# ECAM02-EE2_0.net
KiCad netlist of a schematic drawn in EAGLE
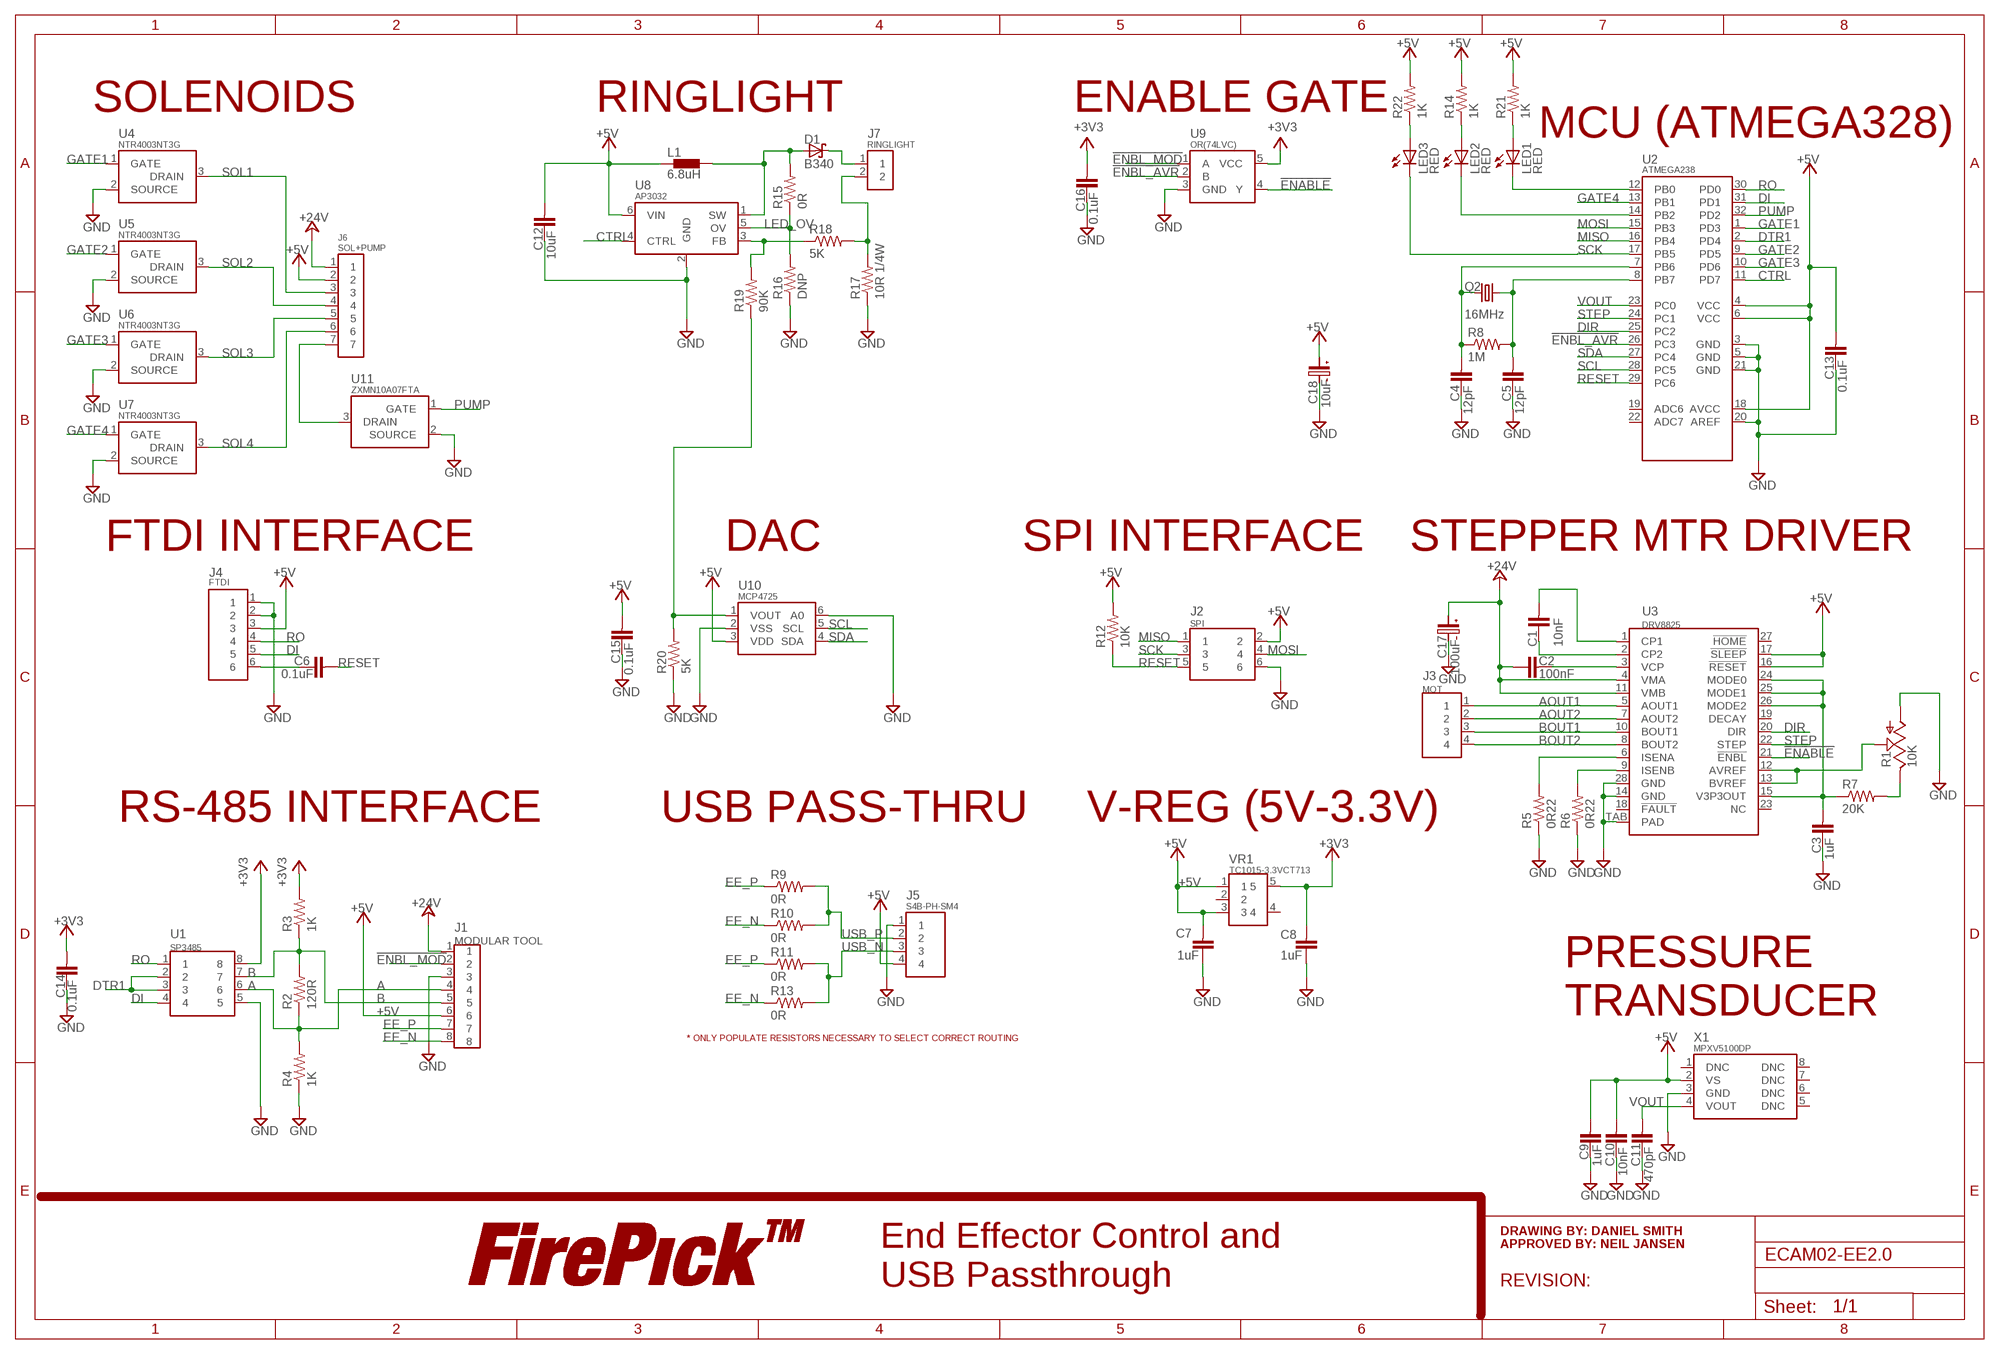
[diagram p0: schematic, sheet 1]

(export (version "E")
  (design (tool "Eeschema 10.0.6"))
  (components
    (comp (ref "C1")
      (value "10nF")
      (footprint "eagle-import:C0603")
      (fields (field (name "PARTNO") "GRM188R71H103KA01D"))
      (libsource (lib "eagle-import") (part "CPL-CAP-X7R-0603-10NF-50V"))
    )
    (comp (ref "C2")
      (value "100nF")
      (footprint "eagle-import:C0603")
      (fields (field (name "PARTNO") "UMK107B7104KA-T"))
      (libsource (lib "eagle-import") (part "CPL-CAP-X7R-0603-100NF-50V"))
    )
    (comp (ref "C3")
      (value "1uF")
      (footprint "eagle-import:C0603")
      (fields (field (name "PARTNO") "UMK107AB7105KA-T"))
      (libsource (lib "eagle-import") (part "CPL-CAP-X5R-0603-1UF-50V"))
    )
    (comp (ref "C4")
      (value "12pF")
      (footprint "eagle-import:C0603")
      (fields (field (name "PARTNO") "GRM1885C1H120FA01J"))
      (libsource (lib "eagle-import") (part "CPL-CAP-C0G-0603-12PF-50V"))
    )
    (comp (ref "C5")
      (value "12pF")
      (footprint "eagle-import:C0603")
      (fields (field (name "PARTNO") "GRM1885C1H120FA01J"))
      (libsource (lib "eagle-import") (part "CPL-CAP-C0G-0603-12PF-50V"))
    )
    (comp (ref "C6")
      (value "0.1uF")
      (footprint "eagle-import:C0603")
      (fields (field (name "PARTNO") "UMK107B7104KA-T"))
      (libsource (lib "eagle-import") (part "CPL-CAP-X7R-0603-100NF-50V"))
    )
    (comp (ref "C7")
      (value "1uF")
      (footprint "eagle-import:C0603")
      (fields (field (name "PARTNO") "UMK107AB7105KA-T"))
      (libsource (lib "eagle-import") (part "CPL-CAP-X5R-0603-1UF-50V"))
    )
    (comp (ref "C8")
      (value "1uF")
      (footprint "eagle-import:C0603")
      (fields (field (name "PARTNO") "UMK107AB7105KA-T"))
      (libsource (lib "eagle-import") (part "CPL-CAP-X5R-0603-1UF-50V"))
    )
    (comp (ref "C9")
      (value "1uF")
      (footprint "eagle-import:C0603")
      (fields (field (name "PARTNO") "UMK107AB7105KA-T"))
      (libsource (lib "eagle-import") (part "CPL-CAP-X5R-0603-1UF-50V"))
    )
    (comp (ref "C10")
      (value "10nF")
      (footprint "eagle-import:C0603")
      (fields (field (name "PARTNO") "GRM188R71H103KA01D"))
      (libsource (lib "eagle-import") (part "CPL-CAP-X7R-0603-10NF-50V"))
    )
    (comp (ref "C11")
      (value "470pF")
      (footprint "eagle-import:C0603")
      (fields (field (name "PARTNO") "GRM188R72A471KA01D"))
      (libsource (lib "eagle-import") (part "CPL-CAP-X7R-0603-470PF-100V"))
    )
    (comp (ref "C12")
      (value "10uF")
      (footprint "eagle-import:C0603")
      (fields (field (name "PARTNO") "GRM188R61C106MA73D"))
      (libsource (lib "eagle-import") (part "CPL-CAP-X5R-0603-10UF-25V"))
    )
    (comp (ref "C13")
      (value "0.1uF")
      (footprint "eagle-import:C0603")
      (fields (field (name "PARTNO") "GMK107BJ104KAHT"))
      (libsource (lib "eagle-import") (part "CPL-CAP-X7R-0603-0.1UF-35V"))
    )
    (comp (ref "C14")
      (value "0.1uF")
      (footprint "eagle-import:C0603")
      (fields (field (name "PARTNO") "GMK107BJ104KAHT"))
      (libsource (lib "eagle-import") (part "CPL-CAP-X7R-0603-0.1UF-35V"))
    )
    (comp (ref "C15")
      (value "0.1uF")
      (footprint "eagle-import:C0603")
      (fields (field (name "PARTNO") "GMK107BJ104KAHT"))
      (libsource (lib "eagle-import") (part "CPL-CAP-X7R-0603-0.1UF-35V"))
    )
    (comp (ref "C16")
      (value "0.1uF")
      (footprint "eagle-import:C0603")
      (fields (field (name "PARTNO") "GMK107BJ104KAHT"))
      (libsource (lib "eagle-import") (part "CPL-CAP-X7R-0603-0.1UF-35V"))
    )
    (comp (ref "C17")
      (value "100uF")
      (footprint "eagle-import:C-SMD-6.3MM")
      (fields (field (name "PARTNO") "EMVA500ADA101MHA0G"))
      (libsource (lib "eagle-import") (part "CPL-CAP-ALU-SMD-100UF-50V"))
    )
    (comp (ref "C18")
      (value "10uF")
      (footprint "eagle-import:C-SMD-6.3MM")
      (fields (field (name "PARTNO") "EMVH350ADA100MF60G"))
      (libsource (lib "eagle-import") (part "CPL-CAP-ALU-6.4MM-10UF-10V"))
    )
    (comp (ref "D1")
      (value "B340")
      (footprint "eagle-import:DIO-SMA")
      (fields (field (name "PARTNO") "B340A-13-F"))
      (libsource (lib "eagle-import") (part "CPL-DIO-B340-13-F-SMA"))
    )
    (comp (ref "J1")
      (value "MODULAR TOOL")
      (footprint "eagle-import:CON-JST-PH-2.0MM-8P-SMT-VRT")
      (fields (field (name "PARTNO") "B8B-PH-SM4-TB(LF)(SN)"))
      (libsource (lib "eagle-import") (part "CPL-CON-JST-2.0MM-8P-SMT-VRT"))
    )
    (comp (ref "J2")
      (value "SPI")
      (footprint "eagle-import:CON-HDR-2X3P")
      (fields (field (name "PARTNO") "67996-206HLF"))
      (libsource (lib "eagle-import") (part "CPL-CON-HEADER-0.1IN-2X3P-M"))
    )
    (comp (ref "J3")
      (value "MOT")
      (footprint "eagle-import:CON-JST-PH-2.0MM-4P-THRU-VRT")
      (fields (field (name "PARTNO") "B4B-PH-K-S(LF)(SN)"))
      (libsource (lib "eagle-import") (part "CPL-CON-JST-2.0MM-4P-M-THRU-VRT"))
    )
    (comp (ref "J4")
      (value "FTDI")
      (footprint "eagle-import:CON-HDR-6POS-MALE")
      (fields (field (name "PARTNO") "S6B-PH-SM4-TB(LF)(SN)"))
      (libsource (lib "eagle-import") (part "CPL-CON-HEADER-0.1IN-6P-M"))
    )
    (comp (ref "J5")
      (value "S4B-PH-SM4")
      (footprint "eagle-import:CON-JST-PH-2.0MM-4P-SMT-VRT")
      (fields (field (name "PARTNO") "S4B-PH-SM4-TB(LF)(SN)"))
      (libsource (lib "eagle-import") (part "CPL-CON-JST-2.0MM-4P-M-SMT-VRT"))
    )
    (comp (ref "J6")
      (value "SOL+PUMP")
      (footprint "eagle-import:CON-JST-PH-2.0MM-7P-SMT-VRT")
      (fields (field (name "PARTNO") "B7B-PH-SM4-TB(LF)(SN)"))
      (libsource (lib "eagle-import") (part "CPL-CON-JST-2.0MM-7P-M-SMT-VRT"))
    )
    (comp (ref "J7")
      (value "RINGLIGHT")
      (footprint "eagle-import:CON-JST-PH-2.0MM-2P-SMT-VRT")
      (fields (field (name "PARTNO") "B2B-PH-SM4-TB(LF)(SN)"))
      (libsource (lib "eagle-import") (part "CPL-CON-JST-2.0MM-2P-M-SMT-VRT"))
    )
    (comp (ref "L1")
      (value "6.8uH")
      (footprint "eagle-import:0603")
      (fields (field (name "PARTNO") "BRL1608T6R8M"))
      (libsource (lib "eagle-import") (part "CPL-IND-6.8UH-250MA"))
    )
    (comp (ref "LED1")
      (value "RED")
      (footprint "eagle-import:LED0603")
      (libsource (lib "eagle-import") (part "CPL-LED-0603-RED"))
    )
    (comp (ref "LED2")
      (value "RED")
      (footprint "eagle-import:LED0603")
      (libsource (lib "eagle-import") (part "CPL-LED-0603-RED"))
    )
    (comp (ref "LED3")
      (value "RED")
      (footprint "eagle-import:LED0603")
      (libsource (lib "eagle-import") (part "CPL-LED-0603-RED"))
    )
    (comp (ref "LOGO2")
      (value "LOGO-FIREPICKLARGE")
      (footprint "eagle-import:LOGO-FIREPICK")
      (libsource (lib "eagle-import") (part "LOGO-FIREPICKLARGE"))
    )
    (comp (ref "Q2")
      (value "16MHz")
      (footprint "eagle-import:HC-49_U-S")
      (fields (field (name "PARTNO") "HCM4916000000ABJT"))
      (libsource (lib "eagle-import") (part "CPL-OSC-CRY-16MHZ-18PF"))
    )
    (comp (ref "R1")
      (value "10K")
      (footprint "eagle-import:TC33X-2")
      (fields (field (name "PARTNO") "TC33X-2-103E"))
      (libsource (lib "eagle-import") (part "TC33X-2"))
    )
    (comp (ref "R2")
      (value "120R")
      (footprint "eagle-import:R0603")
      (fields (field (name "PARTNO") "RC0603FR-07120RL"))
      (libsource (lib "eagle-import") (part "CPL-RES-0603-120-0.1W"))
    )
    (comp (ref "R3")
      (value "1K")
      (footprint "eagle-import:R0603")
      (fields (field (name "PARTNO") "RC0603FR-071KL"))
      (libsource (lib "eagle-import") (part "CPL-RES-0603-1K-0.1W"))
    )
    (comp (ref "R4")
      (value "1K")
      (footprint "eagle-import:R0603")
      (fields (field (name "PARTNO") "RC0603FR-071KL"))
      (libsource (lib "eagle-import") (part "CPL-RES-0603-1K-0.1W"))
    )
    (comp (ref "R5")
      (value "0R22")
      (footprint "eagle-import:R1206")
      (fields (field (name "PARTNO") "RL1206FR-7W0R22L"))
      (libsource (lib "eagle-import") (part "CPL-RES-1206-0.22-0.5W"))
    )
    (comp (ref "R6")
      (value "0R22")
      (footprint "eagle-import:R1206")
      (fields (field (name "PARTNO") "RL1206FR-7W0R22L"))
      (libsource (lib "eagle-import") (part "CPL-RES-1206-0.22-0.5W"))
    )
    (comp (ref "R7")
      (value "20K")
      (footprint "eagle-import:R0603")
      (fields (field (name "PARTNO") "RC0603FR-0722KL"))
      (libsource (lib "eagle-import") (part "CPL-RES-0603-20K-0.1W"))
    )
    (comp (ref "R8")
      (value "1M")
      (footprint "eagle-import:R0603")
      (fields (field (name "PARTNO") "RC0603FR-071ML"))
      (libsource (lib "eagle-import") (part "CPL-RES-0603-1M-0.1W"))
    )
    (comp (ref "R9")
      (value "0R")
      (footprint "eagle-import:R0603")
      (fields (field (name "PARTNO") "RC0603JR-070RL"))
      (libsource (lib "eagle-import") (part "CPL-RES-0603-0-0.1W"))
    )
    (comp (ref "R10")
      (value "0R")
      (footprint "eagle-import:R0603")
      (fields (field (name "PARTNO") "RC0603JR-070RL"))
      (libsource (lib "eagle-import") (part "CPL-RES-0603-0-0.1W"))
    )
    (comp (ref "R11")
      (value "0R")
      (footprint "eagle-import:R0603")
      (fields (field (name "PARTNO") "RC0603JR-070RL"))
      (libsource (lib "eagle-import") (part "CPL-RES-0603-0-0.1W"))
    )
    (comp (ref "R12")
      (value "10K")
      (footprint "eagle-import:R0603")
      (fields (field (name "PARTNO") "RC0603FR-0710KL"))
      (libsource (lib "eagle-import") (part "CPL-RES-0603-10K-0.1W"))
    )
    (comp (ref "R13")
      (value "0R")
      (footprint "eagle-import:R0603")
      (fields (field (name "PARTNO") "RC0603JR-070RL"))
      (libsource (lib "eagle-import") (part "CPL-RES-0603-0-0.1W"))
    )
    (comp (ref "R14")
      (value "1K")
      (footprint "eagle-import:R0603")
      (libsource (lib "eagle-import") (part "CPL-RES-0603-1K-0.1W"))
    )
    (comp (ref "R15")
      (value "0R")
      (footprint "eagle-import:R0603")
      (fields (field (name "PARTNO") "RC0603JR-070RL"))
      (libsource (lib "eagle-import") (part "CPL-RES-0603-0-0.1W"))
    )
    (comp (ref "R16")
      (value "DNP")
      (footprint "eagle-import:R0603")
      (fields (field (name "PARTNO") "RC0603JR-070RL"))
      (libsource (lib "eagle-import") (part "CPL-RES-0603-0-0.1W"))
    )
    (comp (ref "R17")
      (value "10R 1/4W")
      (footprint "eagle-import:R1206")
      (fields (field (name "PARTNO") "RC1206FR-0710RL"))
      (libsource (lib "eagle-import") (part "CPL-RES-1206-10-0.25W1206"))
    )
    (comp (ref "R18")
      (value "5K")
      (footprint "eagle-import:R0603")
      (fields (field (name "PARTNO") "PNM0603E5001BST5"))
      (libsource (lib "eagle-import") (part "CPL-RES-0603-5K-0.1W"))
    )
    (comp (ref "R19")
      (value "90K")
      (footprint "eagle-import:R0603")
      (fields (field (name "PARTNO") "RC0603FR-0790K9L"))
      (libsource (lib "eagle-import") (part "CPL-RES-0603-90K-0.1W"))
    )
    (comp (ref "R20")
      (value "5K")
      (footprint "eagle-import:R0603")
      (fields (field (name "PARTNO") "PNM0603E5001BST5"))
      (libsource (lib "eagle-import") (part "CPL-RES-0603-5K-0.1W"))
    )
    (comp (ref "R21")
      (value "1K")
      (footprint "eagle-import:R0603")
      (libsource (lib "eagle-import") (part "CPL-RES-0603-1K-0.1W"))
    )
    (comp (ref "R22")
      (value "1K")
      (footprint "eagle-import:R0603")
      (libsource (lib "eagle-import") (part "CPL-RES-0603-1K-0.1W"))
    )
    (comp (ref "U1")
      (value "SP3485")
      (footprint "eagle-import:SOICN-8")
      (libsource (lib "eagle-import") (part "SP3485"))
    )
    (comp (ref "U2")
      (value "ATMEGA238")
      (footprint "eagle-import:32-TQF(ATMEGA)")
      (fields (field (name "PARTNO") "ATMEGA328-AUR"))
      (libsource (lib "eagle-import") (part "CPL-MCU-ATMEL-AT328-32TQFP"))
    )
    (comp (ref "U3")
      (value "DRV8825")
      (footprint "eagle-import:28-HSSOP")
      (fields (field (name "PARTNO") "DRV8825PWPR"))
      (libsource (lib "eagle-import") (part "CPL-MDR-DRV8825"))
    )
    (comp (ref "U4")
      (value "NTR4003NT3G")
      (footprint "eagle-import:SOT-23-3")
      (libsource (lib "eagle-import") (part "CPL-MOSFET-NCH-SOT23NTR4003N"))
    )
    (comp (ref "U5")
      (value "NTR4003NT3G")
      (footprint "eagle-import:SOT-23-3")
      (libsource (lib "eagle-import") (part "CPL-MOSFET-NCH-SOT23NTR4003N"))
    )
    (comp (ref "U6")
      (value "NTR4003NT3G")
      (footprint "eagle-import:SOT-23-3")
      (libsource (lib "eagle-import") (part "CPL-MOSFET-NCH-SOT23NTR4003N"))
    )
    (comp (ref "U7")
      (value "NTR4003NT3G")
      (footprint "eagle-import:SOT-23-3")
      (libsource (lib "eagle-import") (part "CPL-MOSFET-NCH-SOT23NTR4003N"))
    )
    (comp (ref "U8")
      (value "AP3032")
      (footprint "eagle-import:SOT-23-6")
      (fields (field (name "PARTNO") "AP3032KTR-G1"))
      (libsource (lib "eagle-import") (part "CPL-LED-DRIVER-WHT-AP3032"))
    )
    (comp (ref "U9")
      (value "OR(74LVC)")
      (footprint "eagle-import:SOT-23-5")
      (fields (field (name "PARTNO") "SN74LVC1G32DBVR"))
      (libsource (lib "eagle-import") (part "CPL-IC-LOGIC-OR-1CH-74LVC"))
    )
    (comp (ref "U10")
      (value "MCP4725")
      (footprint "eagle-import:SOT-23-6")
      (fields (field (name "PARTNO") "MCP4725A0T-E/CH"))
      (libsource (lib "eagle-import") (part "CPL-DAC-12BIT-SOT23"))
    )
    (comp (ref "U11")
      (value "ZXMN10A07FTA")
      (footprint "eagle-import:SOT-23-3")
      (libsource (lib "eagle-import") (part "CPL-MOSFET-NCH-SOT23ZXMN10A07FTA"))
    )
    (comp (ref "VR1")
      (value "TC1015-3.3VCT713")
      (footprint "eagle-import:SOT-23-5")
      (libsource (lib "eagle-import") (part "CPL-REG-LIN-3.3V-0.1A"))
    )
    (comp (ref "X1")
      (value "MPXV5100DP")
      (footprint "eagle-import:8-SMD")
      (libsource (lib "eagle-import") (part "CPL-SEN-PRS-MPXV5100DP"))
    )
  )
  (nets
    (net (code "1") (name "+3V3") (class "Default")
      (node (ref "C14") (pin "2") (pinfunction "2_2") (pintype "passive"))
      (node (ref "C16") (pin "2") (pinfunction "2_2") (pintype "passive"))
      (node (ref "C8") (pin "2") (pinfunction "2_2") (pintype "passive"))
      (node (ref "R3") (pin "2") (pinfunction "2_2") (pintype "passive"))
      (node (ref "U1") (pin "8") (pinfunction "8_8") (pintype "bidirectional"))
      (node (ref "U9") (pin "5") (pinfunction "VCC_5") (pintype "bidirectional"))
      (node (ref "VR1") (pin "5") (pinfunction "5_5") (pintype "passive"))
    )
    (net (code "2") (name "+5V") (class "Default")
      (node (ref "C10") (pin "2") (pinfunction "2_2") (pintype "passive"))
      (node (ref "C12") (pin "2") (pinfunction "2_2") (pintype "passive"))
      (node (ref "C13") (pin "2") (pinfunction "2_2") (pintype "passive"))
      (node (ref "C15") (pin "2") (pinfunction "2_2") (pintype "passive"))
      (node (ref "C18") (pin "POS") (pinfunction "POS_POS") (pintype "passive"))
      (node (ref "C7") (pin "2") (pinfunction "2_2") (pintype "passive"))
      (node (ref "C9") (pin "2") (pinfunction "2_2") (pintype "passive"))
      (node (ref "J1") (pin "6") (pinfunction "6_6") (pintype "passive"))
      (node (ref "J2") (pin "2") (pinfunction "2_2") (pintype "passive"))
      (node (ref "J4") (pin "3") (pinfunction "3_3") (pintype "bidirectional"))
      (node (ref "J5") (pin "4") (pinfunction "4_4") (pintype "passive"))
      (node (ref "J6") (pin "2") (pinfunction "2_2") (pintype "bidirectional"))
      (node (ref "L1") (pin "1") (pinfunction "1_1") (pintype "passive"))
      (node (ref "R12") (pin "2") (pinfunction "2_2") (pintype "passive"))
      (node (ref "R14") (pin "2") (pinfunction "2_2") (pintype "passive"))
      (node (ref "R21") (pin "2") (pinfunction "2_2") (pintype "passive"))
      (node (ref "R22") (pin "2") (pinfunction "2_2") (pintype "passive"))
      (node (ref "U10") (pin "3") (pinfunction "VDD_3") (pintype "bidirectional"))
      (node (ref "U2") (pin "18") (pinfunction "AVCC_18") (pintype "bidirectional"))
      (node (ref "U2") (pin "4") (pinfunction "VCC_4") (pintype "bidirectional"))
      (node (ref "U2") (pin "6") (pinfunction "VCC_6") (pintype "bidirectional"))
      (node (ref "U3") (pin "16") (pinfunction "~{RESET}_16") (pintype "bidirectional"))
      (node (ref "U3") (pin "17") (pinfunction "~{SLEEP}_17") (pintype "bidirectional"))
      (node (ref "U8") (pin "6") (pinfunction "VIN_6") (pintype "bidirectional"))
      (node (ref "VR1") (pin "1") (pinfunction "1_1") (pintype "passive"))
      (node (ref "VR1") (pin "3") (pinfunction "3_3") (pintype "passive"))
      (node (ref "X1") (pin "2") (pinfunction "VS_2") (pintype "bidirectional"))
    )
    (net (code "3") (name "+24V") (class "Default")
      (node (ref "C17") (pin "POS") (pinfunction "POS_POS") (pintype "passive"))
      (node (ref "C2") (pin "1") (pinfunction "1_1") (pintype "passive"))
      (node (ref "J1") (pin "1") (pinfunction "1_1") (pintype "passive"))
      (node (ref "J6") (pin "1") (pinfunction "1_1") (pintype "bidirectional"))
      (node (ref "U3") (pin "11") (pinfunction "VMB_11") (pintype "bidirectional"))
      (node (ref "U3") (pin "4") (pinfunction "VMA_4") (pintype "bidirectional"))
    )
    (net (code "4") (name "/A") (class "Default")
      (node (ref "J1") (pin "4") (pinfunction "4_4") (pintype "passive"))
      (node (ref "R2") (pin "1") (pinfunction "1_1") (pintype "passive"))
      (node (ref "R4") (pin "2") (pinfunction "2_2") (pintype "passive"))
      (node (ref "U1") (pin "6") (pinfunction "6_6") (pintype "bidirectional"))
    )
    (net (code "5") (name "/AOUT1") (class "Default")
      (node (ref "J3") (pin "1") (pinfunction "1_1") (pintype "passive"))
      (node (ref "U3") (pin "5") (pinfunction "AOUT1_5") (pintype "bidirectional"))
    )
    (net (code "6") (name "/AOUT2") (class "Default")
      (node (ref "J3") (pin "2") (pinfunction "2_2") (pintype "passive"))
      (node (ref "U3") (pin "7") (pinfunction "AOUT2_7") (pintype "bidirectional"))
    )
    (net (code "7") (name "/B") (class "Default")
      (node (ref "J1") (pin "5") (pinfunction "5_5") (pintype "passive"))
      (node (ref "R2") (pin "2") (pinfunction "2_2") (pintype "passive"))
      (node (ref "R3") (pin "1") (pinfunction "1_1") (pintype "passive"))
      (node (ref "U1") (pin "7") (pinfunction "7_7") (pintype "bidirectional"))
    )
    (net (code "8") (name "/BOUT1") (class "Default")
      (node (ref "J3") (pin "3") (pinfunction "3_3") (pintype "passive"))
      (node (ref "U3") (pin "10") (pinfunction "BOUT1_10") (pintype "bidirectional"))
    )
    (net (code "9") (name "/BOUT2") (class "Default")
      (node (ref "J3") (pin "4") (pinfunction "4_4") (pintype "passive"))
      (node (ref "U3") (pin "8") (pinfunction "BOUT2_8") (pintype "bidirectional"))
    )
    (net (code "10") (name "/CTRL") (class "Default")
      (node (ref "U2") (pin "11") (pinfunction "PD7_11") (pintype "bidirectional"))
      (node (ref "U8") (pin "4") (pinfunction "CTRL_4") (pintype "bidirectional"))
    )
    (net (code "11") (name "/DI") (class "Default")
      (node (ref "J4") (pin "5") (pinfunction "5_5") (pintype "bidirectional"))
      (node (ref "U1") (pin "4") (pinfunction "4_4") (pintype "bidirectional"))
      (node (ref "U2") (pin "31") (pinfunction "PD1_31") (pintype "bidirectional"))
    )
    (net (code "12") (name "/DIR") (class "Default")
      (node (ref "U2") (pin "25") (pinfunction "PC2_25") (pintype "bidirectional"))
      (node (ref "U3") (pin "20") (pinfunction "DIR_20") (pintype "bidirectional"))
    )
    (net (code "13") (name "/DTR1") (class "Default")
      (node (ref "U1") (pin "2") (pinfunction "2_2") (pintype "bidirectional"))
      (node (ref "U1") (pin "3") (pinfunction "3_3") (pintype "bidirectional"))
      (node (ref "U2") (pin "2") (pinfunction "PD4_2") (pintype "bidirectional"))
    )
    (net (code "14") (name "/EE_N") (class "Default")
      (node (ref "J1") (pin "8") (pinfunction "8_8") (pintype "passive"))
      (node (ref "R10") (pin "1") (pinfunction "1_1") (pintype "passive"))
      (node (ref "R13") (pin "1") (pinfunction "1_1") (pintype "passive"))
    )
    (net (code "15") (name "/EE_P") (class "Default")
      (node (ref "J1") (pin "7") (pinfunction "7_7") (pintype "passive"))
      (node (ref "R11") (pin "1") (pinfunction "1_1") (pintype "passive"))
      (node (ref "R9") (pin "1") (pinfunction "1_1") (pintype "passive"))
    )
    (net (code "16") (name "/GATE1") (class "Default")
      (node (ref "U2") (pin "1") (pinfunction "PD3_1") (pintype "bidirectional"))
      (node (ref "U4") (pin "1") (pinfunction "GATE_1") (pintype "bidirectional"))
    )
    (net (code "17") (name "/GATE2") (class "Default")
      (node (ref "U2") (pin "9") (pinfunction "PD5_9") (pintype "bidirectional"))
      (node (ref "U5") (pin "1") (pinfunction "GATE_1") (pintype "bidirectional"))
    )
    (net (code "18") (name "/GATE3") (class "Default")
      (node (ref "U2") (pin "10") (pinfunction "PD6_10") (pintype "bidirectional"))
      (node (ref "U6") (pin "1") (pinfunction "GATE_1") (pintype "bidirectional"))
    )
    (net (code "19") (name "/GATE4") (class "Default")
      (node (ref "U2") (pin "13") (pinfunction "PB1_13") (pintype "bidirectional"))
      (node (ref "U7") (pin "1") (pinfunction "GATE_1") (pintype "bidirectional"))
    )
    (net (code "20") (name "/LED_OV") (class "Default")
      (node (ref "R15") (pin "1") (pinfunction "1_1") (pintype "passive"))
      (node (ref "R16") (pin "2") (pinfunction "2_2") (pintype "passive"))
      (node (ref "U8") (pin "5") (pinfunction "OV_5") (pintype "bidirectional"))
    )
    (net (code "21") (name "/MISO") (class "Default")
      (node (ref "J2") (pin "1") (pinfunction "1_1") (pintype "passive"))
      (node (ref "U2") (pin "16") (pinfunction "PB4_16") (pintype "bidirectional"))
    )
    (net (code "22") (name "/MOSI") (class "Default")
      (node (ref "J2") (pin "4") (pinfunction "4_4") (pintype "passive"))
      (node (ref "U2") (pin "15") (pinfunction "PB3_15") (pintype "bidirectional"))
    )
    (net (code "23") (name "/PUMP") (class "Default")
      (node (ref "U11") (pin "1") (pinfunction "GATE_1") (pintype "bidirectional"))
      (node (ref "U2") (pin "32") (pinfunction "PD2_32") (pintype "bidirectional"))
    )
    (net (code "24") (name "/RESET") (class "Default")
      (node (ref "C6") (pin "2") (pinfunction "2_2") (pintype "passive"))
      (node (ref "J2") (pin "5") (pinfunction "5_5") (pintype "passive"))
      (node (ref "R12") (pin "1") (pinfunction "1_1") (pintype "passive"))
      (node (ref "U2") (pin "29") (pinfunction "PC6_29") (pintype "bidirectional"))
    )
    (net (code "25") (name "/RO") (class "Default")
      (node (ref "J4") (pin "4") (pinfunction "4_4") (pintype "bidirectional"))
      (node (ref "U1") (pin "1") (pinfunction "1_1") (pintype "bidirectional"))
      (node (ref "U2") (pin "30") (pinfunction "PD0_30") (pintype "bidirectional"))
    )
    (net (code "26") (name "/SCK") (class "Default")
      (node (ref "J2") (pin "3") (pinfunction "3_3") (pintype "passive"))
      (node (ref "LED3") (pin "C") (pinfunction "C_C") (pintype "passive"))
      (node (ref "U2") (pin "17") (pinfunction "PB5_17") (pintype "bidirectional"))
    )
    (net (code "27") (name "/SCL") (class "Default")
      (node (ref "U10") (pin "5") (pinfunction "SCL_5") (pintype "bidirectional"))
      (node (ref "U2") (pin "28") (pinfunction "PC5_28") (pintype "bidirectional"))
    )
    (net (code "28") (name "/SDA") (class "Default")
      (node (ref "U10") (pin "4") (pinfunction "SDA_4") (pintype "bidirectional"))
      (node (ref "U2") (pin "27") (pinfunction "PC4_27") (pintype "bidirectional"))
    )
    (net (code "29") (name "/SOL1") (class "Default")
      (node (ref "J6") (pin "3") (pinfunction "3_3") (pintype "bidirectional"))
      (node (ref "U4") (pin "3") (pinfunction "DRAIN_3") (pintype "bidirectional"))
    )
    (net (code "30") (name "/SOL2") (class "Default")
      (node (ref "J6") (pin "4") (pinfunction "4_4") (pintype "bidirectional"))
      (node (ref "U5") (pin "3") (pinfunction "DRAIN_3") (pintype "bidirectional"))
    )
    (net (code "31") (name "/SOL3") (class "Default")
      (node (ref "J6") (pin "5") (pinfunction "5_5") (pintype "bidirectional"))
      (node (ref "U6") (pin "3") (pinfunction "DRAIN_3") (pintype "bidirectional"))
    )
    (net (code "32") (name "/SOL4") (class "Default")
      (node (ref "J6") (pin "6") (pinfunction "6_6") (pintype "bidirectional"))
      (node (ref "U7") (pin "3") (pinfunction "DRAIN_3") (pintype "bidirectional"))
    )
    (net (code "33") (name "/STEP") (class "Default")
      (node (ref "U2") (pin "24") (pinfunction "PC1_24") (pintype "bidirectional"))
      (node (ref "U3") (pin "22") (pinfunction "STEP_22") (pintype "bidirectional"))
    )
    (net (code "34") (name "/USB_N") (class "Default")
      (node (ref "J5") (pin "3") (pinfunction "3_3") (pintype "passive"))
      (node (ref "R11") (pin "2") (pinfunction "2_2") (pintype "passive"))
      (node (ref "R13") (pin "2") (pinfunction "2_2") (pintype "passive"))
    )
    (net (code "35") (name "/USB_P") (class "Default")
      (node (ref "J5") (pin "2") (pinfunction "2_2") (pintype "passive"))
      (node (ref "R10") (pin "2") (pinfunction "2_2") (pintype "passive"))
      (node (ref "R9") (pin "2") (pinfunction "2_2") (pintype "passive"))
    )
    (net (code "36") (name "/VOUT") (class "Default")
      (node (ref "C11") (pin "2") (pinfunction "2_2") (pintype "passive"))
      (node (ref "U2") (pin "23") (pinfunction "PC0_23") (pintype "bidirectional"))
      (node (ref "X1") (pin "4") (pinfunction "VOUT_4") (pintype "bidirectional"))
    )
    (net (code "37") (name "/~{ENABLE}") (class "Default")
      (node (ref "U3") (pin "21") (pinfunction "~{ENBL}_21") (pintype "bidirectional"))
      (node (ref "U9") (pin "4") (pinfunction "Y_4") (pintype "bidirectional"))
    )
    (net (code "38") (name "/~{ENBL_AVR}") (class "Default")
      (node (ref "U2") (pin "26") (pinfunction "PC3_26") (pintype "bidirectional"))
      (node (ref "U9") (pin "2") (pinfunction "B_2") (pintype "bidirectional"))
    )
    (net (code "39") (name "/~{ENBL_MOD}") (class "Default")
      (node (ref "J1") (pin "2") (pinfunction "2_2") (pintype "passive"))
      (node (ref "U9") (pin "1") (pinfunction "A_1") (pintype "bidirectional"))
    )
    (net (code "40") (name "GND") (class "Default")
      (node (ref "C10") (pin "1") (pinfunction "1_1") (pintype "passive"))
      (node (ref "C11") (pin "1") (pinfunction "1_1") (pintype "passive"))
      (node (ref "C12") (pin "1") (pinfunction "1_1") (pintype "passive"))
      (node (ref "C13") (pin "1") (pinfunction "1_1") (pintype "passive"))
      (node (ref "C14") (pin "1") (pinfunction "1_1") (pintype "passive"))
      (node (ref "C15") (pin "1") (pinfunction "1_1") (pintype "passive"))
      (node (ref "C16") (pin "1") (pinfunction "1_1") (pintype "passive"))
      (node (ref "C17") (pin "NEG") (pinfunction "NEG_NEG") (pintype "passive"))
      (node (ref "C18") (pin "NEG") (pinfunction "NEG_NEG") (pintype "passive"))
      (node (ref "C3") (pin "1") (pinfunction "1_1") (pintype "passive"))
      (node (ref "C4") (pin "1") (pinfunction "1_1") (pintype "passive"))
      (node (ref "C5") (pin "1") (pinfunction "1_1") (pintype "passive"))
      (node (ref "C7") (pin "1") (pinfunction "1_1") (pintype "passive"))
      (node (ref "C8") (pin "1") (pinfunction "1_1") (pintype "passive"))
      (node (ref "C9") (pin "1") (pinfunction "1_1") (pintype "passive"))
      (node (ref "J1") (pin "3") (pinfunction "3_3") (pintype "passive"))
      (node (ref "J2") (pin "6") (pinfunction "6_6") (pintype "passive"))
      (node (ref "J4") (pin "1") (pinfunction "1_1") (pintype "bidirectional"))
      (node (ref "J4") (pin "2") (pinfunction "2_2") (pintype "bidirectional"))
      (node (ref "J5") (pin "1") (pinfunction "1_1") (pintype "passive"))
      (node (ref "R1") (pin "1") (pinfunction "A_1") (pintype "passive"))
      (node (ref "R16") (pin "1") (pinfunction "1_1") (pintype "passive"))
      (node (ref "R17") (pin "1") (pinfunction "1_1") (pintype "passive"))
      (node (ref "R20") (pin "1") (pinfunction "1_1") (pintype "passive"))
      (node (ref "R4") (pin "1") (pinfunction "1_1") (pintype "passive"))
      (node (ref "R5") (pin "1") (pinfunction "1_1") (pintype "passive"))
      (node (ref "R6") (pin "1") (pinfunction "1_1") (pintype "passive"))
      (node (ref "U1") (pin "5") (pinfunction "5_5") (pintype "bidirectional"))
      (node (ref "U10") (pin "2") (pinfunction "VSS_2") (pintype "bidirectional"))
      (node (ref "U10") (pin "6") (pinfunction "A0_6") (pintype "bidirectional"))
      (node (ref "U11") (pin "2") (pinfunction "SOURCE_2") (pintype "bidirectional"))
      (node (ref "U2") (pin "20") (pinfunction "AREF_20") (pintype "bidirectional"))
      (node (ref "U2") (pin "21") (pinfunction "GND_21") (pintype "bidirectional"))
      (node (ref "U2") (pin "3") (pinfunction "GND_3") (pintype "bidirectional"))
      (node (ref "U2") (pin "5") (pinfunction "GND_5") (pintype "bidirectional"))
      (node (ref "U3") (pin "14") (pinfunction "GND_14") (pintype "bidirectional"))
      (node (ref "U3") (pin "28") (pinfunction "GND_28") (pintype "bidirectional"))
      (node (ref "U3") (pin "TAB") (pinfunction "PAD_TAB") (pintype "bidirectional"))
      (node (ref "U4") (pin "2") (pinfunction "SOURCE_2") (pintype "bidirectional"))
      (node (ref "U5") (pin "2") (pinfunction "SOURCE_2") (pintype "bidirectional"))
      (node (ref "U6") (pin "2") (pinfunction "SOURCE_2") (pintype "bidirectional"))
      (node (ref "U7") (pin "2") (pinfunction "SOURCE_2") (pintype "bidirectional"))
      (node (ref "U8") (pin "2") (pinfunction "GND_2") (pintype "bidirectional"))
      (node (ref "U9") (pin "3") (pinfunction "GND_3") (pintype "bidirectional"))
      (node (ref "X1") (pin "3") (pinfunction "GND_3") (pintype "bidirectional"))
    )
    (net (code "41") (name "Net-(C6-Pad1)") (class "Default")
      (node (ref "C6") (pin "1") (pinfunction "1_1") (pintype "passive"))
      (node (ref "J4") (pin "6") (pinfunction "6_6") (pintype "bidirectional"))
    )
    (net (code "42") (name "Net-(D1-A)") (class "Default")
      (node (ref "D1") (pin "POS") (pinfunction "A_POS") (pintype "passive"))
      (node (ref "L1") (pin "2") (pinfunction "2_2") (pintype "passive"))
      (node (ref "R15") (pin "2") (pinfunction "2_2") (pintype "passive"))
      (node (ref "U8") (pin "1") (pinfunction "SW_1") (pintype "bidirectional"))
    )
    (net (code "43") (name "Net-(D1-C)") (class "Default")
      (node (ref "D1") (pin "NEG") (pinfunction "C_NEG") (pintype "passive"))
      (node (ref "J7") (pin "1") (pinfunction "1_1") (pintype "passive"))
    )
    (net (code "44") (name "Net-(J7-Pad2)") (class "Default")
      (node (ref "J7") (pin "2") (pinfunction "2_2") (pintype "passive"))
      (node (ref "R17") (pin "2") (pinfunction "2_2") (pintype "passive"))
      (node (ref "R18") (pin "2") (pinfunction "2_2") (pintype "passive"))
    )
    (net (code "45") (name "Net-(LED1-PadA)") (class "Default")
      (node (ref "LED1") (pin "A") (pinfunction "A_A") (pintype "passive"))
      (node (ref "R21") (pin "1") (pinfunction "1_1") (pintype "passive"))
    )
    (net (code "46") (name "Net-(LED2-PadA)") (class "Default")
      (node (ref "LED2") (pin "A") (pinfunction "A_A") (pintype "passive"))
      (node (ref "R14") (pin "1") (pinfunction "1_1") (pintype "passive"))
    )
    (net (code "47") (name "Net-(LED3-PadA)") (class "Default")
      (node (ref "LED3") (pin "A") (pinfunction "A_A") (pintype "passive"))
      (node (ref "R22") (pin "1") (pinfunction "1_1") (pintype "passive"))
    )
    (net (code "48") (name "Net-(R1-E)") (class "Default")
      (node (ref "R1") (pin "3") (pinfunction "E_3") (pintype "passive"))
      (node (ref "R7") (pin "2") (pinfunction "2_2") (pintype "passive"))
    )
    (net (code "49") (name "Net-(R1-S)") (class "Default")
      (node (ref "R1") (pin "2") (pinfunction "S_2") (pintype "passive"))
      (node (ref "U3") (pin "12") (pinfunction "AVREF_12") (pintype "bidirectional"))
      (node (ref "U3") (pin "13") (pinfunction "BVREF_13") (pintype "bidirectional"))
    )
    (net (code "50") (name "Net-(U2-PB0)") (class "Default")
      (node (ref "LED1") (pin "C") (pinfunction "C_C") (pintype "passive"))
      (node (ref "U2") (pin "12") (pinfunction "PB0_12") (pintype "bidirectional"))
    )
    (net (code "51") (name "Net-(U2-PB2)") (class "Default")
      (node (ref "LED2") (pin "C") (pinfunction "C_C") (pintype "passive"))
      (node (ref "U2") (pin "14") (pinfunction "PB2_14") (pintype "bidirectional"))
    )
    (net (code "52") (name "Net-(U2-PB6)") (class "Default")
      (node (ref "C4") (pin "2") (pinfunction "2_2") (pintype "passive"))
      (node (ref "Q2") (pin "1") (pinfunction "1_1") (pintype "passive"))
      (node (ref "R8") (pin "1") (pinfunction "1_1") (pintype "passive"))
      (node (ref "U2") (pin "7") (pinfunction "PB6_7") (pintype "bidirectional"))
    )
    (net (code "53") (name "Net-(U2-PB7)") (class "Default")
      (node (ref "C5") (pin "2") (pinfunction "2_2") (pintype "passive"))
      (node (ref "Q2") (pin "2") (pinfunction "2_2") (pintype "passive"))
      (node (ref "R8") (pin "2") (pinfunction "2_2") (pintype "passive"))
      (node (ref "U2") (pin "8") (pinfunction "PB7_8") (pintype "bidirectional"))
    )
    (net (code "54") (name "Net-(U3-CP1)") (class "Default")
      (node (ref "C1") (pin "2") (pinfunction "2_2") (pintype "passive"))
      (node (ref "U3") (pin "1") (pinfunction "CP1_1") (pintype "bidirectional"))
    )
    (net (code "55") (name "Net-(U3-CP2)") (class "Default")
      (node (ref "C1") (pin "1") (pinfunction "1_1") (pintype "passive"))
      (node (ref "U3") (pin "2") (pinfunction "CP2_2") (pintype "bidirectional"))
    )
    (net (code "56") (name "Net-(U3-ISENA)") (class "Default")
      (node (ref "R5") (pin "2") (pinfunction "2_2") (pintype "passive"))
      (node (ref "U3") (pin "6") (pinfunction "ISENA_6") (pintype "bidirectional"))
    )
    (net (code "57") (name "Net-(U3-ISENB)") (class "Default")
      (node (ref "R6") (pin "2") (pinfunction "2_2") (pintype "passive"))
      (node (ref "U3") (pin "9") (pinfunction "ISENB_9") (pintype "bidirectional"))
    )
    (net (code "58") (name "Net-(U3-MODE0)") (class "Default")
      (node (ref "C3") (pin "2") (pinfunction "2_2") (pintype "passive"))
      (node (ref "R7") (pin "1") (pinfunction "1_1") (pintype "passive"))
      (node (ref "U3") (pin "15") (pinfunction "V3P3OUT_15") (pintype "bidirectional"))
      (node (ref "U3") (pin "24") (pinfunction "MODE0_24") (pintype "bidirectional"))
      (node (ref "U3") (pin "25") (pinfunction "MODE1_25") (pintype "bidirectional"))
      (node (ref "U3") (pin "26") (pinfunction "MODE2_26") (pintype "bidirectional"))
    )
    (net (code "59") (name "Net-(U3-VCP)") (class "Default")
      (node (ref "C2") (pin "2") (pinfunction "2_2") (pintype "passive"))
      (node (ref "U3") (pin "3") (pinfunction "VCP_3") (pintype "bidirectional"))
    )
    (net (code "60") (name "Net-(U8-FB)") (class "Default")
      (node (ref "R18") (pin "1") (pinfunction "1_1") (pintype "passive"))
      (node (ref "R19") (pin "2") (pinfunction "2_2") (pintype "passive"))
      (node (ref "U8") (pin "3") (pinfunction "FB_3") (pintype "bidirectional"))
    )
    (net (code "61") (name "Net-(U10-VOUT)") (class "Default")
      (node (ref "R19") (pin "1") (pinfunction "1_1") (pintype "passive"))
      (node (ref "R20") (pin "2") (pinfunction "2_2") (pintype "passive"))
      (node (ref "U10") (pin "1") (pinfunction "VOUT_1") (pintype "bidirectional"))
    )
    (net (code "62") (name "Net-(U11-DRAIN)") (class "Default")
      (node (ref "J6") (pin "7") (pinfunction "7_7") (pintype "bidirectional"))
      (node (ref "U11") (pin "3") (pinfunction "DRAIN_3") (pintype "bidirectional"))
    )
    (net (code "63") (name "unconnected-(U2-ADC6-Pad19)") (class "Default")
      (node (ref "U2") (pin "19") (pinfunction "ADC6_19") (pintype "bidirectional"))
    )
    (net (code "64") (name "unconnected-(U2-ADC7-Pad22)") (class "Default")
      (node (ref "U2") (pin "22") (pinfunction "ADC7_22") (pintype "bidirectional"))
    )
    (net (code "65") (name "unconnected-(U3-DECAY-Pad19)") (class "Default")
      (node (ref "U3") (pin "19") (pinfunction "DECAY_19") (pintype "bidirectional"))
    )
    (net (code "66") (name "unconnected-(U3-NC-Pad23)") (class "Default")
      (node (ref "U3") (pin "23") (pinfunction "NC_23") (pintype "bidirectional"))
    )
    (net (code "67") (name "unconnected-(U3-~{FAULT}-Pad18)") (class "Default")
      (node (ref "U3") (pin "18") (pinfunction "~{FAULT}_18") (pintype "bidirectional"))
    )
    (net (code "68") (name "unconnected-(U3-~{HOME}-Pad27)") (class "Default")
      (node (ref "U3") (pin "27") (pinfunction "~{HOME}_27") (pintype "bidirectional"))
    )
    (net (code "69") (name "unconnected-(VR1-Pad2)") (class "Default")
      (node (ref "VR1") (pin "2") (pinfunction "2_2") (pintype "passive"))
    )
    (net (code "70") (name "unconnected-(VR1-Pad4)") (class "Default")
      (node (ref "VR1") (pin "4") (pinfunction "4_4") (pintype "passive"))
    )
    (net (code "71") (name "unconnected-(X1-DNC-Pad1)") (class "Default")
      (node (ref "X1") (pin "1") (pinfunction "DNC_1") (pintype "bidirectional"))
    )
    (net (code "72") (name "unconnected-(X1-DNC-Pad5)") (class "Default")
      (node (ref "X1") (pin "5") (pinfunction "DNC_5") (pintype "bidirectional"))
    )
    (net (code "73") (name "unconnected-(X1-DNC-Pad6)") (class "Default")
      (node (ref "X1") (pin "6") (pinfunction "DNC_6") (pintype "bidirectional"))
    )
    (net (code "74") (name "unconnected-(X1-DNC-Pad7)") (class "Default")
      (node (ref "X1") (pin "7") (pinfunction "DNC_7") (pintype "bidirectional"))
    )
    (net (code "75") (name "unconnected-(X1-DNC-Pad8)") (class "Default")
      (node (ref "X1") (pin "8") (pinfunction "DNC_8") (pintype "bidirectional"))
    )
  )
)
